# Gate_Driver_1.net
KiCad netlist of a schematic drawn in Altium Designer
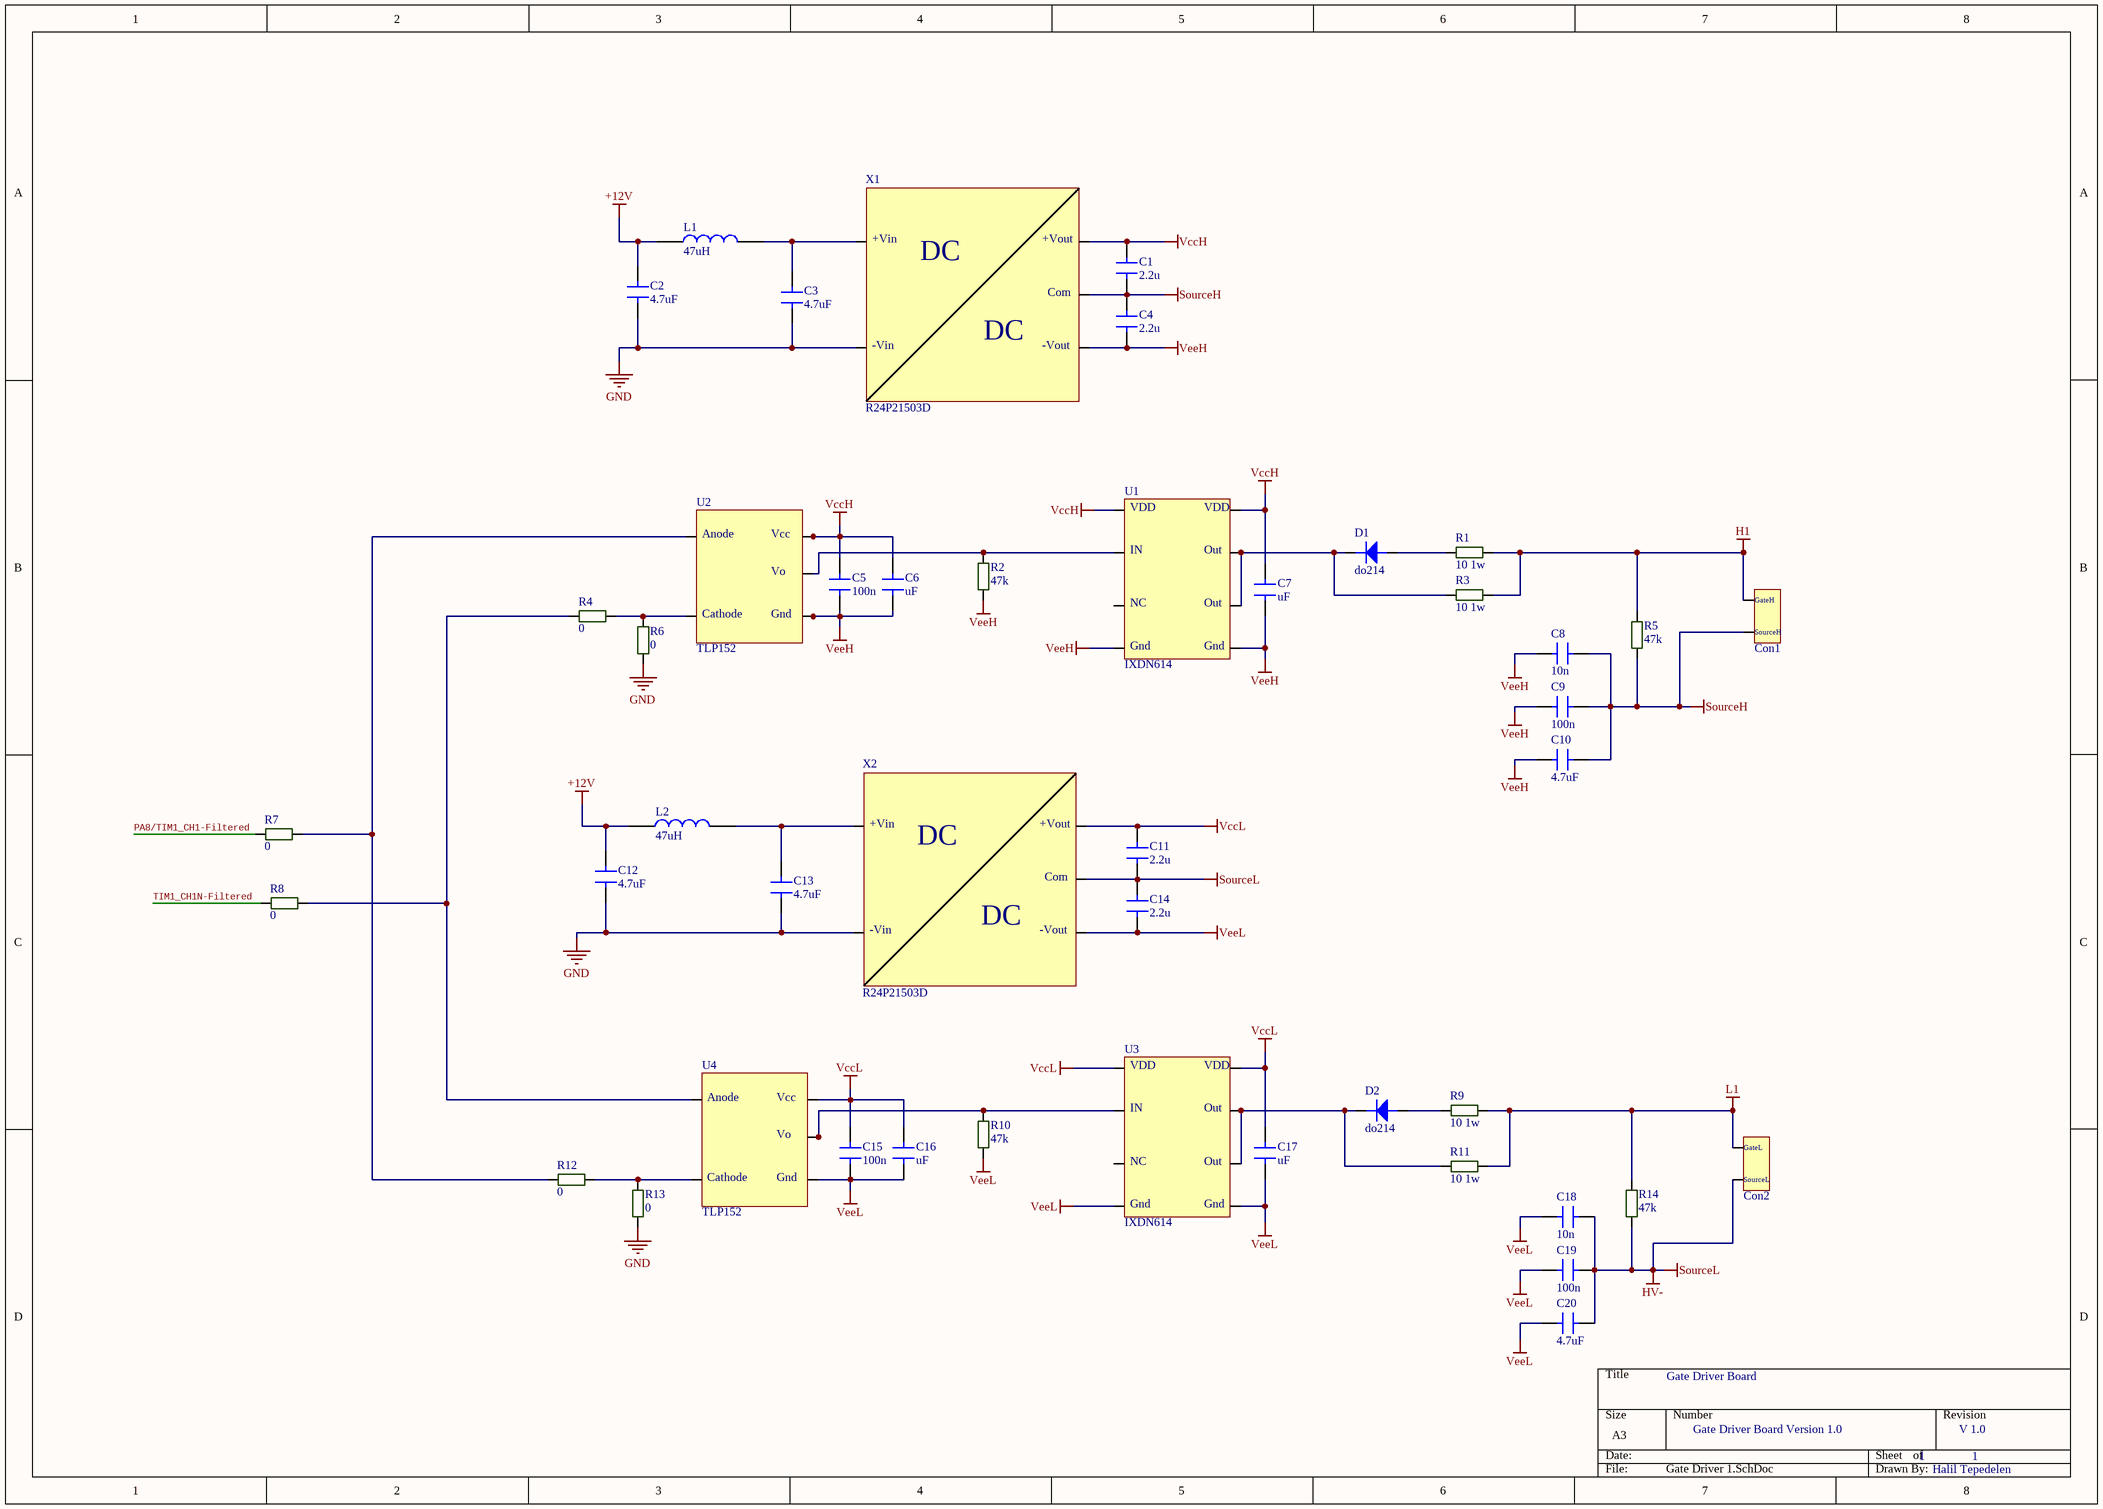
[diagram p0: Gate Driver 1.SchDoc]

(export (version "E")
  (design (tool "Eeschema 10.0.6"))
  (components
    (comp (ref "C1")
      (value "2.2u")
      (footprint "C-0805")
      (libsource (lib "Gate Driver Board") (part "C-0805"))
    )
    (comp (ref "C2")
      (value "4.7uF")
      (footprint "C-1206")
      (description "MLCC (3216) 1206 4.7uF 50VDC ±10% X7R")
      (fields (field (name "ÖZDISAN PART NUMBER") "CL31B475KBHNNNE") (field (name "MANUFACTURER") "SAMSUNG"))
      (libsource (lib "Gate Driver Board") (part "Cap1206"))
    )
    (comp (ref "C3")
      (value "4.7uF")
      (footprint "C-1206")
      (description "MLCC (3216) 1206 4.7uF 50VDC ±10% X7R")
      (fields (field (name "ÖZDISAN PART NUMBER") "CL31B475KBHNNNE") (field (name "MANUFACTURER") "SAMSUNG"))
      (libsource (lib "Gate Driver Board") (part "Cap1206"))
    )
    (comp (ref "C4")
      (value "2.2u")
      (footprint "C-0805")
      (libsource (lib "Gate Driver Board") (part "C-0805"))
    )
    (comp (ref "C5")
      (value "100n")
      (footprint "C-0805")
      (libsource (lib "Gate Driver Board") (part "C-0805"))
    )
    (comp (ref "C6") (value "uF") (footprint "C-1206") (libsource (lib "Gate Driver Board") (part "C-1206")))
    (comp (ref "C7") (value "uF") (footprint "C-1206") (libsource (lib "Gate Driver Board") (part "C-1206")))
    (comp (ref "C8") (value "10n") (footprint "C-0805") (libsource (lib "Gate Driver Board") (part "C-0805")))
    (comp (ref "C9")
      (value "100n")
      (footprint "C-0805")
      (libsource (lib "Gate Driver Board") (part "C-0805"))
    )
    (comp (ref "C10")
      (value "4.7uF")
      (footprint "C-1206")
      (description "MLCC (3216) 1206 4.7uF 50VDC ±10% X7R")
      (fields (field (name "ÖZDISAN PART NUMBER") " CL31B475KBHNNNE") (field (name "MANUFACTURER") "SAMSUNG"))
      (libsource (lib "Gate Driver Board") (part "Cap1206"))
    )
    (comp (ref "C11")
      (value "2.2u")
      (footprint "C-0805")
      (libsource (lib "Gate Driver Board") (part "C-0805"))
    )
    (comp (ref "C12")
      (value "4.7uF")
      (footprint "C-1206")
      (description "MLCC (3216) 1206 4.7uF 50VDC ±10% X7R")
      (fields (field (name "ÖZDISAN PART NUMBER") "CL31B475KBHNNNE") (field (name "MANUFACTURER") "SAMSUNG"))
      (libsource (lib "Gate Driver Board") (part "Cap1206"))
    )
    (comp (ref "C13")
      (value "4.7uF")
      (footprint "C-1206")
      (description "MLCC (3216) 1206 4.7uF 50VDC ±10% X7R")
      (fields (field (name "ÖZDISAN PART NUMBER") " CL31B475KBHNNNE") (field (name "MANUFACTURER") "SAMSUNG"))
      (libsource (lib "Gate Driver Board") (part "Cap1206"))
    )
    (comp (ref "C14")
      (value "2.2u")
      (footprint "C-0805")
      (libsource (lib "Gate Driver Board") (part "C-0805"))
    )
    (comp (ref "C15")
      (value "100n")
      (footprint "C-0805")
      (libsource (lib "Gate Driver Board") (part "C-0805"))
    )
    (comp (ref "C16") (value "uF") (footprint "C-1206") (libsource (lib "Gate Driver Board") (part "C-1206")))
    (comp (ref "C17") (value "uF") (footprint "C-1206") (libsource (lib "Gate Driver Board") (part "C-1206")))
    (comp (ref "C18")
      (value "10n")
      (footprint "C-0805")
      (libsource (lib "Gate Driver Board") (part "C-0805"))
    )
    (comp (ref "C19")
      (value "100n")
      (footprint "C-0805")
      (libsource (lib "Gate Driver Board") (part "C-0805"))
    )
    (comp (ref "C20")
      (value "4.7uF")
      (footprint "C-1206")
      (description "MLCC (3216) 1206 4.7uF 50VDC ±10% X7R")
      (fields (field (name "ÖZDISAN PART NUMBER") "CL31B475KBHNNNE") (field (name "MANUFACTURER") "SAMSUNG"))
      (libsource (lib "Gate Driver Board") (part "Cap1206"))
    )
    (comp (ref "Con1")
      (value "Connector2_1")
      (footprint "Conn")
      (libsource (lib "Gate Driver Board") (part "Connector2_1"))
    )
    (comp (ref "Con2")
      (value "Connector2_2")
      (footprint "Conn")
      (libsource (lib "Gate Driver Board") (part "Connector2_2"))
    )
    (comp (ref "D1")
      (value "do214")
      (footprint "DO-214AC")
      (description "DIODE FAST SWITCHING Single 150mA 75V SMT SOD323")
      (libsource (lib "Gate Driver Board") (part "do214"))
    )
    (comp (ref "D2")
      (value "do214")
      (footprint "DO-214AC")
      (description "DIODE FAST SWITCHING Single 150mA 75V SMT SOD323")
      (libsource (lib "Gate Driver Board") (part "do214"))
    )
    (comp (ref "L1")
      (value "47uH")
      (footprint "WE-TPC_282892")
      (libsource (lib "Gate Driver Board") (part "inductor"))
    )
    (comp (ref "L2")
      (value "47uH")
      (footprint "WE-TPC_282892")
      (libsource (lib "Gate Driver Board") (part "inductor"))
    )
    (comp (ref "R1")
      (value "10 1w")
      (footprint "R-2512")
      (libsource (lib "Gate Driver Board") (part "R-2512"))
    )
    (comp (ref "R2")
      (value "47k")
      (footprint "R-0805")
      (description "RES.(2012) 0805 47K Ohms 5% 1/8W-S 100PPM")
      (fields (field (name "MANUFACTURER") "ROYALOHM") (field (name "ÖZDISAN PART NUMBER") "0805S8J0473T5E"))
      (libsource (lib "Gate Driver Board") (part "Res0805"))
    )
    (comp (ref "R3")
      (value "10 1w")
      (footprint "R-2512")
      (libsource (lib "Gate Driver Board") (part "R-2512"))
    )
    (comp (ref "R4")
      (value "0")
      (footprint "R-0805")
      (description "RES.(2012) 0805 0 Ohms 5% 1/8W-S 800PPM")
      (fields (field (name "MANUFACTURER") "ROYALOHM") (field (name "ÖZDISAN PART NUMBER") "0805S8J0000T5E"))
      (libsource (lib "Gate Driver Board") (part "Res0805"))
    )
    (comp (ref "R5")
      (value "47k")
      (footprint "R-0805")
      (description "RES.(2012) 0805 47K Ohms 5% 1/8W-S 100PPM")
      (fields (field (name "ÖZDISAN PART NUMBER") "0805S8J0473T5E") (field (name "MANUFACTURER") "ROYALOHM"))
      (libsource (lib "Gate Driver Board") (part "Res0805"))
    )
    (comp (ref "R6")
      (value "0")
      (footprint "R-0805")
      (description "RES.(2012) 0805 0 Ohms 5% 1/8W-S 800PPM")
      (fields (field (name "MANUFACTURER") "ROYALOHM") (field (name "ÖZDISAN PART NUMBER") "0805S8J0000T5E"))
      (libsource (lib "Gate Driver Board") (part "Res0805"))
    )
    (comp (ref "R7")
      (value "0")
      (footprint "R-0805")
      (description "RES.(2012) 0805 0 Ohms 5% 1/8W-S 800PPM")
      (fields (field (name "MANUFACTURER") "ROYALOHM") (field (name "ÖZDISAN PART NUMBER") "0805S8J0000T5E"))
      (libsource (lib "Gate Driver Board") (part "Res0805"))
    )
    (comp (ref "R8")
      (value "0")
      (footprint "R-0805")
      (description "RES.(2012) 0805 0 Ohms 5% 1/8W-S 800PPM")
      (fields (field (name "MANUFACTURER") "ROYALOHM") (field (name "ÖZDISAN PART NUMBER") "0805S8J0000T5E"))
      (libsource (lib "Gate Driver Board") (part "Res0805"))
    )
    (comp (ref "R9")
      (value "10 1w")
      (footprint "R-2512")
      (libsource (lib "Gate Driver Board") (part "R-2512"))
    )
    (comp (ref "R10")
      (value "47k")
      (footprint "R-0805")
      (description "RES.(2012) 0805 47K Ohms 5% 1/8W-S 100PPM")
      (fields (field (name "ÖZDISAN PART NUMBER") "0805S8J0473T5E") (field (name "MANUFACTURER") "ROYALOHM"))
      (libsource (lib "Gate Driver Board") (part "Res0805"))
    )
    (comp (ref "R11")
      (value "10 1w")
      (footprint "R-2512")
      (libsource (lib "Gate Driver Board") (part "R-2512"))
    )
    (comp (ref "R12")
      (value "0")
      (footprint "R-0805")
      (description "RES.(2012) 0805 0 Ohms 5% 1/8W-S 800PPM")
      (fields (field (name "MANUFACTURER") "ROYALOHM") (field (name "ÖZDISAN PART NUMBER") "0805S8J0000T5E"))
      (libsource (lib "Gate Driver Board") (part "Res0805"))
    )
    (comp (ref "R13")
      (value "0")
      (footprint "R-0805")
      (description "RES.(2012) 0805 0 Ohms 5% 1/8W-S 800PPM")
      (fields (field (name "MANUFACTURER") "ROYALOHM") (field (name "ÖZDISAN PART NUMBER") "0805S8J0000T5E"))
      (libsource (lib "Gate Driver Board") (part "Res0805"))
    )
    (comp (ref "R14")
      (value "47k")
      (footprint "R-0805")
      (description "RES.(2012) 0805 47K Ohms 5% 1/8W-S 100PPM")
      (fields (field (name "ÖZDISAN PART NUMBER") "0805S8J0473T5E") (field (name "MANUFACTURER") "ROYALOHM"))
      (libsource (lib "Gate Driver Board") (part "Res0805"))
    )
    (comp (ref "U1")
      (value "IXDN614")
      (footprint "FAN3122 Soic8")
      (description "14A 8SOIC EXP MTL NON INVERTING")
      (fields
        (field (name "MANUFACTURER") "Ixys Clare")
        (field (name "MANUFACTURER PART NUMBER") "IXDN614SITR")
      )
      (libsource (lib "Gate Driver Board") (part "IXDN614SITR"))
    )
    (comp (ref "U2")
      (value "TLP152")
      (footprint "TLP152")
      (description "OPTOISO 3.75KV GATE DRIVER 6SO-5")
      (fields
        (field (name "MANUFACTURER") "Toshiba")
        (field (name "MANUFACTURER PART NUMBER") "TLP152(TPL,E")
      )
      (libsource (lib "Gate Driver Board") (part "TLP152(TPL,E"))
    )
    (comp (ref "U3")
      (value "IXDN614")
      (footprint "FAN3122 Soic8")
      (description "14A 8SOIC EXP MTL NON INVERTING")
      (fields
        (field (name "MANUFACTURER") "Ixys Clare")
        (field (name "MANUFACTURER PART NUMBER") "IXDN614SITR")
      )
      (libsource (lib "Gate Driver Board") (part "IXDN614SITR"))
    )
    (comp (ref "U4")
      (value "TLP152")
      (footprint "TLP152")
      (description "OPTOISO 3.75KV GATE DRIVER 6SO-5")
      (fields
        (field (name "MANUFACTURER") "Toshiba")
        (field (name "MANUFACTURER PART NUMBER") "TLP152(TPL,E")
      )
      (libsource (lib "Gate Driver Board") (part "TLP152(TPL,E"))
    )
    (comp (ref "X1")
      (value "R24P21503D")
      (footprint "SIP7")
      (fields (field (name "MANUFACTURER") "Recom"))
      (libsource (lib "Gate Driver Board") (part "R24P21503D"))
    )
    (comp (ref "X2")
      (value "R24P21503D")
      (footprint "SIP7")
      (fields (field (name "MANUFACTURER") "Recom"))
      (libsource (lib "Gate Driver Board") (part "R24P21503D"))
    )
  )
  (nets
    (net (code "1") (name "+12V") (class "Default")
      (node (ref "C12") (pin "2") (pinfunction "2_2") (pintype "passive"))
      (node (ref "C2") (pin "2") (pinfunction "2_2") (pintype "passive"))
      (node (ref "L1") (pin "1") (pinfunction "1_1") (pintype "passive"))
      (node (ref "L2") (pin "1") (pinfunction "1_1") (pintype "passive"))
    )
    (net (code "2") (name "/PA8{slash}TIM1_CH1-Filtered") (class "Default")
      (node (ref "R7") (pin "1") (pinfunction "1_1") (pintype "passive"))
    )
    (net (code "3") (name "/TIM1_CH1N-Filtered") (class "Default")
      (node (ref "R8") (pin "1") (pinfunction "1_1") (pintype "passive"))
    )
    (net (code "4") (name "GND") (class "Default")
      (node (ref "C12") (pin "1") (pinfunction "1_1") (pintype "passive"))
      (node (ref "C13") (pin "1") (pinfunction "1_1") (pintype "passive"))
      (node (ref "C2") (pin "1") (pinfunction "1_1") (pintype "passive"))
      (node (ref "C3") (pin "1") (pinfunction "1_1") (pintype "passive"))
      (node (ref "R13") (pin "1") (pinfunction "1_1") (pintype "passive"))
      (node (ref "R6") (pin "1") (pinfunction "1_1") (pintype "passive"))
      (node (ref "X1") (pin "2") (pinfunction "2_2") (pintype "passive"))
      (node (ref "X2") (pin "2") (pinfunction "2_2") (pintype "passive"))
    )
    (net (code "5") (name "H1") (class "Default")
      (node (ref "Con1") (pin "1") (pinfunction "1_1") (pintype "passive"))
      (node (ref "R1") (pin "2") (pinfunction "2_2") (pintype "passive"))
      (node (ref "R3") (pin "2") (pinfunction "2_2") (pintype "passive"))
      (node (ref "R5") (pin "2") (pinfunction "2_2") (pintype "passive"))
    )
    (net (code "6") (name "HV-") (class "Default")
      (node (ref "C11") (pin "1") (pinfunction "1_1") (pintype "passive"))
      (node (ref "C14") (pin "2") (pinfunction "2_2") (pintype "passive"))
      (node (ref "C18") (pin "1") (pinfunction "1_1") (pintype "passive"))
      (node (ref "C19") (pin "1") (pinfunction "1_1") (pintype "passive"))
      (node (ref "C20") (pin "2") (pinfunction "2_2") (pintype "passive"))
      (node (ref "Con2") (pin "2") (pinfunction "2_2") (pintype "passive"))
      (node (ref "R14") (pin "1") (pinfunction "1_1") (pintype "passive"))
      (node (ref "X2") (pin "6") (pinfunction "6_6") (pintype "passive"))
    )
    (net (code "7") (name "L1") (class "Default")
      (node (ref "Con2") (pin "1") (pinfunction "1_1") (pintype "passive"))
      (node (ref "R11") (pin "2") (pinfunction "2_2") (pintype "passive"))
      (node (ref "R14") (pin "2") (pinfunction "2_2") (pintype "passive"))
      (node (ref "R9") (pin "2") (pinfunction "2_2") (pintype "passive"))
    )
    (net (code "8") (name "Net-(C3-Pad2)") (class "Default")
      (node (ref "C3") (pin "2") (pinfunction "2_2") (pintype "passive"))
      (node (ref "L1") (pin "2") (pinfunction "2_2") (pintype "passive"))
      (node (ref "X1") (pin "1") (pinfunction "1_1") (pintype "passive"))
    )
    (net (code "9") (name "Net-(C13-Pad2)") (class "Default")
      (node (ref "C13") (pin "2") (pinfunction "2_2") (pintype "passive"))
      (node (ref "L2") (pin "2") (pinfunction "2_2") (pintype "passive"))
      (node (ref "X2") (pin "1") (pinfunction "1_1") (pintype "passive"))
    )
    (net (code "10") (name "Net-(D1-Pada)") (class "Default")
      (node (ref "D1") (pin "a") (pinfunction "a_a") (pintype "passive"))
      (node (ref "R1") (pin "1") (pinfunction "1_1") (pintype "passive"))
    )
    (net (code "11") (name "Net-(D1-Padk)") (class "Default")
      (node (ref "D1") (pin "k") (pinfunction "k_k") (pintype "passive"))
      (node (ref "R3") (pin "1") (pinfunction "1_1") (pintype "passive"))
      (node (ref "U1") (pin "6") (pinfunction "6_6") (pintype "passive"))
      (node (ref "U1") (pin "7") (pinfunction "7_7") (pintype "passive"))
    )
    (net (code "12") (name "Net-(D2-Pada)") (class "Default")
      (node (ref "D2") (pin "a") (pinfunction "a_a") (pintype "passive"))
      (node (ref "R9") (pin "1") (pinfunction "1_1") (pintype "passive"))
    )
    (net (code "13") (name "Net-(D2-Padk)") (class "Default")
      (node (ref "D2") (pin "k") (pinfunction "k_k") (pintype "passive"))
      (node (ref "R11") (pin "1") (pinfunction "1_1") (pintype "passive"))
      (node (ref "U3") (pin "6") (pinfunction "6_6") (pintype "passive"))
      (node (ref "U3") (pin "7") (pinfunction "7_7") (pintype "passive"))
    )
    (net (code "14") (name "Net-(R2-Pad2)") (class "Default")
      (node (ref "R2") (pin "2") (pinfunction "2_2") (pintype "passive"))
      (node (ref "U1") (pin "2") (pinfunction "2_2") (pintype "passive"))
      (node (ref "U2") (pin "4") (pinfunction "4_4") (pintype "passive"))
    )
    (net (code "15") (name "Net-(R4-Pad1)") (class "Default")
      (node (ref "R4") (pin "1") (pinfunction "1_1") (pintype "passive"))
      (node (ref "R8") (pin "2") (pinfunction "2_2") (pintype "passive"))
      (node (ref "U4") (pin "1") (pinfunction "1_1") (pintype "passive"))
    )
    (net (code "16") (name "Net-(R4-Pad2)") (class "Default")
      (node (ref "R4") (pin "2") (pinfunction "2_2") (pintype "passive"))
      (node (ref "R6") (pin "2") (pinfunction "2_2") (pintype "passive"))
      (node (ref "U2") (pin "2") (pinfunction "2_2") (pintype "passive"))
    )
    (net (code "17") (name "Net-(R10-Pad2)") (class "Default")
      (node (ref "R10") (pin "2") (pinfunction "2_2") (pintype "passive"))
      (node (ref "U3") (pin "2") (pinfunction "2_2") (pintype "passive"))
      (node (ref "U4") (pin "4") (pinfunction "4_4") (pintype "passive"))
    )
    (net (code "18") (name "Net-(R12-Pad1)") (class "Default")
      (node (ref "R12") (pin "1") (pinfunction "1_1") (pintype "passive"))
      (node (ref "R7") (pin "2") (pinfunction "2_2") (pintype "passive"))
      (node (ref "U2") (pin "1") (pinfunction "1_1") (pintype "passive"))
    )
    (net (code "19") (name "Net-(R12-Pad2)") (class "Default")
      (node (ref "R12") (pin "2") (pinfunction "2_2") (pintype "passive"))
      (node (ref "R13") (pin "2") (pinfunction "2_2") (pintype "passive"))
      (node (ref "U4") (pin "2") (pinfunction "2_2") (pintype "passive"))
    )
    (net (code "20") (name "SourceH") (class "Default")
      (node (ref "C1") (pin "1") (pinfunction "1_1") (pintype "passive"))
      (node (ref "C10") (pin "2") (pinfunction "2_2") (pintype "passive"))
      (node (ref "C4") (pin "2") (pinfunction "2_2") (pintype "passive"))
      (node (ref "C8") (pin "1") (pinfunction "1_1") (pintype "passive"))
      (node (ref "C9") (pin "1") (pinfunction "1_1") (pintype "passive"))
      (node (ref "Con1") (pin "2") (pinfunction "2_2") (pintype "passive"))
      (node (ref "R5") (pin "1") (pinfunction "1_1") (pintype "passive"))
      (node (ref "X1") (pin "6") (pinfunction "6_6") (pintype "passive"))
    )
    (net (code "21") (name "VccH") (class "Default")
      (node (ref "C1") (pin "2") (pinfunction "2_2") (pintype "passive"))
      (node (ref "C5") (pin "2") (pinfunction "2_2") (pintype "passive"))
      (node (ref "C6") (pin "2") (pinfunction "2_2") (pintype "passive"))
      (node (ref "C7") (pin "2") (pinfunction "2_2") (pintype "passive"))
      (node (ref "U1") (pin "1") (pinfunction "1_1") (pintype "passive"))
      (node (ref "U1") (pin "8") (pinfunction "8_8") (pintype "passive"))
      (node (ref "U2") (pin "5") (pinfunction "5_5") (pintype "passive"))
      (node (ref "X1") (pin "7") (pinfunction "7_7") (pintype "passive"))
    )
    (net (code "22") (name "VccL") (class "Default")
      (node (ref "C11") (pin "2") (pinfunction "2_2") (pintype "passive"))
      (node (ref "C15") (pin "2") (pinfunction "2_2") (pintype "passive"))
      (node (ref "C16") (pin "2") (pinfunction "2_2") (pintype "passive"))
      (node (ref "C17") (pin "2") (pinfunction "2_2") (pintype "passive"))
      (node (ref "U3") (pin "1") (pinfunction "1_1") (pintype "passive"))
      (node (ref "U3") (pin "8") (pinfunction "8_8") (pintype "passive"))
      (node (ref "U4") (pin "5") (pinfunction "5_5") (pintype "passive"))
      (node (ref "X2") (pin "7") (pinfunction "7_7") (pintype "passive"))
    )
    (net (code "23") (name "VeeH") (class "Default")
      (node (ref "C10") (pin "1") (pinfunction "1_1") (pintype "passive"))
      (node (ref "C4") (pin "1") (pinfunction "1_1") (pintype "passive"))
      (node (ref "C5") (pin "1") (pinfunction "1_1") (pintype "passive"))
      (node (ref "C6") (pin "1") (pinfunction "1_1") (pintype "passive"))
      (node (ref "C7") (pin "1") (pinfunction "1_1") (pintype "passive"))
      (node (ref "C8") (pin "2") (pinfunction "2_2") (pintype "passive"))
      (node (ref "C9") (pin "2") (pinfunction "2_2") (pintype "passive"))
      (node (ref "R2") (pin "1") (pinfunction "1_1") (pintype "passive"))
      (node (ref "U1") (pin "4") (pinfunction "4_4") (pintype "passive"))
      (node (ref "U1") (pin "5") (pinfunction "5_5") (pintype "passive"))
      (node (ref "U2") (pin "3") (pinfunction "3_3") (pintype "passive"))
      (node (ref "X1") (pin "5") (pinfunction "5_5") (pintype "passive"))
    )
    (net (code "24") (name "VeeL") (class "Default")
      (node (ref "C14") (pin "1") (pinfunction "1_1") (pintype "passive"))
      (node (ref "C15") (pin "1") (pinfunction "1_1") (pintype "passive"))
      (node (ref "C16") (pin "1") (pinfunction "1_1") (pintype "passive"))
      (node (ref "C17") (pin "1") (pinfunction "1_1") (pintype "passive"))
      (node (ref "C18") (pin "2") (pinfunction "2_2") (pintype "passive"))
      (node (ref "C19") (pin "2") (pinfunction "2_2") (pintype "passive"))
      (node (ref "C20") (pin "1") (pinfunction "1_1") (pintype "passive"))
      (node (ref "R10") (pin "1") (pinfunction "1_1") (pintype "passive"))
      (node (ref "U3") (pin "4") (pinfunction "4_4") (pintype "passive"))
      (node (ref "U3") (pin "5") (pinfunction "5_5") (pintype "passive"))
      (node (ref "U4") (pin "3") (pinfunction "3_3") (pintype "passive"))
      (node (ref "X2") (pin "5") (pinfunction "5_5") (pintype "passive"))
    )
    (net (code "25") (name "unconnected-(U1-Pad3)") (class "Default")
      (node (ref "U1") (pin "3") (pinfunction "3_3") (pintype "passive"))
    )
    (net (code "26") (name "unconnected-(U3-Pad3)") (class "Default")
      (node (ref "U3") (pin "3") (pinfunction "3_3") (pintype "passive"))
    )
  )
)
